# low_side_driver.net
KiCad netlist of a schematic drawn in EAGLE
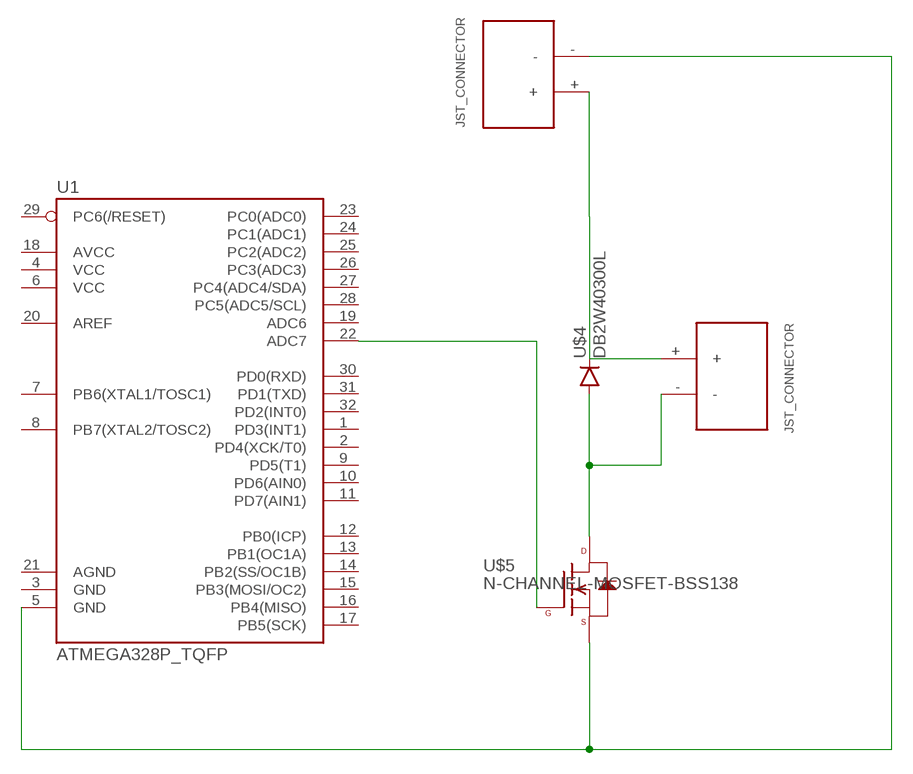
[diagram p0: schematic, sheet 1]

(export (version "E")
  (design (tool "Eeschema 10.0.6"))
  (components
    (comp (ref "U$1")
      (value "JST_CONNECTOR_FEMALE")
      (footprint "eagle-import:JST_CONNECTOR_FEMALE")
      (libsource (lib "eagle-import") (part "JST_CONNECTOR_FEMALE"))
    )
    (comp (ref "U$3")
      (value "JST_CONNECTOR_FEMALE")
      (footprint "eagle-import:JST_CONNECTOR_FEMALE")
      (libsource (lib "eagle-import") (part "JST_CONNECTOR_FEMALE"))
    )
    (comp (ref "U$4")
      (value "DB2W40300L")
      (footprint "eagle-import:MINI2-F3-B")
      (libsource (lib "eagle-import") (part "DB2W40300L"))
    )
    (comp (ref "U$5")
      (value "N-CHANNEL-MOSFET-BSS138")
      (footprint "eagle-import:SOT23-3")
      (libsource (lib "eagle-import") (part "N-CHANNEL-MOSFET-BSS138"))
    )
    (comp (ref "U1")
      (value "ATMEGA328P_TQFP")
      (footprint "eagle-import:TQFP32-08")
      (libsource (lib "eagle-import") (part "ATMEGA328P_TQFP"))
    )
  )
  (nets
    (net (code "1") (name "Net-(U$4-GPIN)") (class "Default")
      (node (ref "U$1") (pin "+") (pinfunction "+_+") (pintype "bidirectional"))
      (node (ref "U$3") (pin "+") (pinfunction "+_+") (pintype "bidirectional"))
      (node (ref "U$4") (pin "NEG") (pinfunction "GPIN_NEG") (pintype "passive"))
    )
    (net (code "2") (name "Net-(U$4-PPIN)") (class "Default")
      (node (ref "U$3") (pin "-") (pinfunction "-_-") (pintype "bidirectional"))
      (node (ref "U$4") (pin "POS") (pinfunction "PPIN_POS") (pintype "passive"))
      (node (ref "U$5") (pin "3") (pinfunction "D_3") (pintype "passive"))
    )
    (net (code "3") (name "Net-(U$5-G)") (class "Default")
      (node (ref "U$5") (pin "1") (pinfunction "G_1") (pintype "passive"))
      (node (ref "U1") (pin "22") (pinfunction "ADC7_22") (pintype "bidirectional"))
    )
    (net (code "4") (name "Net-(U$5-S)") (class "Default")
      (node (ref "U$1") (pin "-") (pinfunction "-_-") (pintype "bidirectional"))
      (node (ref "U$5") (pin "2") (pinfunction "S_2") (pintype "passive"))
      (node (ref "U1") (pin "5") (pinfunction "GND_5") (pintype "bidirectional"))
    )
    (net (code "5") (name "unconnected-(U1-ADC6-Pad19)") (class "Default")
      (node (ref "U1") (pin "19") (pinfunction "ADC6_19") (pintype "bidirectional"))
    )
    (net (code "6") (name "unconnected-(U1-AGND-Pad21)") (class "Default")
      (node (ref "U1") (pin "21") (pinfunction "AGND_21") (pintype "bidirectional"))
    )
    (net (code "7") (name "unconnected-(U1-AREF-Pad20)") (class "Default")
      (node (ref "U1") (pin "20") (pinfunction "AREF_20") (pintype "bidirectional"))
    )
    (net (code "8") (name "unconnected-(U1-AVCC-Pad18)") (class "Default")
      (node (ref "U1") (pin "18") (pinfunction "AVCC_18") (pintype "bidirectional"))
    )
    (net (code "9") (name "unconnected-(U1-GND-Pad3)") (class "Default")
      (node (ref "U1") (pin "3") (pinfunction "GND_3") (pintype "bidirectional"))
    )
    (net (code "10") (name "unconnected-(U1-PB0(ICP)-Pad12)") (class "Default")
      (node (ref "U1") (pin "12") (pinfunction "PB0(ICP)_12") (pintype "bidirectional"))
    )
    (net (code "11") (name "unconnected-(U1-PB1(OC1A)-Pad13)") (class "Default")
      (node (ref "U1") (pin "13") (pinfunction "PB1(OC1A)_13") (pintype "bidirectional"))
    )
    (net (code "12") (name "unconnected-(U1-PB2(SS{slash}OC1B)-Pad14)") (class "Default")
      (node (ref "U1") (pin "14") (pinfunction "PB2(SS/OC1B)_14") (pintype "bidirectional"))
    )
    (net (code "13") (name "unconnected-(U1-PB3(MOSI{slash}OC2)-Pad15)") (class "Default")
      (node (ref "U1") (pin "15") (pinfunction "PB3(MOSI/OC2)_15") (pintype "bidirectional"))
    )
    (net (code "14") (name "unconnected-(U1-PB4(MISO)-Pad16)") (class "Default")
      (node (ref "U1") (pin "16") (pinfunction "PB4(MISO)_16") (pintype "bidirectional"))
    )
    (net (code "15") (name "unconnected-(U1-PB5(SCK)-Pad17)") (class "Default")
      (node (ref "U1") (pin "17") (pinfunction "PB5(SCK)_17") (pintype "bidirectional"))
    )
    (net (code "16") (name "unconnected-(U1-PB6(XTAL1{slash}TOSC1)-Pad7)") (class "Default")
      (node (ref "U1") (pin "7") (pinfunction "PB6(XTAL1/TOSC1)_7") (pintype "bidirectional"))
    )
    (net (code "17") (name "unconnected-(U1-PB7(XTAL2{slash}TOSC2)-Pad8)") (class "Default")
      (node (ref "U1") (pin "8") (pinfunction "PB7(XTAL2/TOSC2)_8") (pintype "bidirectional"))
    )
    (net (code "18") (name "unconnected-(U1-PC0(ADC0)-Pad23)") (class "Default")
      (node (ref "U1") (pin "23") (pinfunction "PC0(ADC0)_23") (pintype "bidirectional"))
    )
    (net (code "19") (name "unconnected-(U1-PC1(ADC1)-Pad24)") (class "Default")
      (node (ref "U1") (pin "24") (pinfunction "PC1(ADC1)_24") (pintype "bidirectional"))
    )
    (net (code "20") (name "unconnected-(U1-PC2(ADC2)-Pad25)") (class "Default")
      (node (ref "U1") (pin "25") (pinfunction "PC2(ADC2)_25") (pintype "bidirectional"))
    )
    (net (code "21") (name "unconnected-(U1-PC3(ADC3)-Pad26)") (class "Default")
      (node (ref "U1") (pin "26") (pinfunction "PC3(ADC3)_26") (pintype "bidirectional"))
    )
    (net (code "22") (name "unconnected-(U1-PC4(ADC4{slash}SDA)-Pad27)") (class "Default")
      (node (ref "U1") (pin "27") (pinfunction "PC4(ADC4/SDA)_27") (pintype "bidirectional"))
    )
    (net (code "23") (name "unconnected-(U1-PC5(ADC5{slash}SCL)-Pad28)") (class "Default")
      (node (ref "U1") (pin "28") (pinfunction "PC5(ADC5/SCL)_28") (pintype "bidirectional"))
    )
    (net (code "24") (name "unconnected-(U1-PC6({slash}RESET)-Pad29)") (class "Default")
      (node (ref "U1") (pin "29") (pinfunction "PC6(/RESET)_29") (pintype "bidirectional"))
    )
    (net (code "25") (name "unconnected-(U1-PD0(RXD)-Pad30)") (class "Default")
      (node (ref "U1") (pin "30") (pinfunction "PD0(RXD)_30") (pintype "bidirectional"))
    )
    (net (code "26") (name "unconnected-(U1-PD1(TXD)-Pad31)") (class "Default")
      (node (ref "U1") (pin "31") (pinfunction "PD1(TXD)_31") (pintype "bidirectional"))
    )
    (net (code "27") (name "unconnected-(U1-PD2(INT0)-Pad32)") (class "Default")
      (node (ref "U1") (pin "32") (pinfunction "PD2(INT0)_32") (pintype "bidirectional"))
    )
    (net (code "28") (name "unconnected-(U1-PD3(INT1)-Pad1)") (class "Default")
      (node (ref "U1") (pin "1") (pinfunction "PD3(INT1)_1") (pintype "bidirectional"))
    )
    (net (code "29") (name "unconnected-(U1-PD4(XCK{slash}T0)-Pad2)") (class "Default")
      (node (ref "U1") (pin "2") (pinfunction "PD4(XCK/T0)_2") (pintype "bidirectional"))
    )
    (net (code "30") (name "unconnected-(U1-PD5(T1)-Pad9)") (class "Default")
      (node (ref "U1") (pin "9") (pinfunction "PD5(T1)_9") (pintype "bidirectional"))
    )
    (net (code "31") (name "unconnected-(U1-PD6(AIN0)-Pad10)") (class "Default")
      (node (ref "U1") (pin "10") (pinfunction "PD6(AIN0)_10") (pintype "bidirectional"))
    )
    (net (code "32") (name "unconnected-(U1-PD7(AIN1)-Pad11)") (class "Default")
      (node (ref "U1") (pin "11") (pinfunction "PD7(AIN1)_11") (pintype "bidirectional"))
    )
    (net (code "33") (name "unconnected-(U1-VCC-Pad4)") (class "Default")
      (node (ref "U1") (pin "4") (pinfunction "VCC_4") (pintype "bidirectional"))
    )
    (net (code "34") (name "unconnected-(U1-VCC-Pad6)") (class "Default")
      (node (ref "U1") (pin "6") (pinfunction "VCC_6") (pintype "bidirectional"))
    )
  )
)
